# Sensor_Probe_Panel.net
KiCad netlist of a schematic drawn in Altium Designer
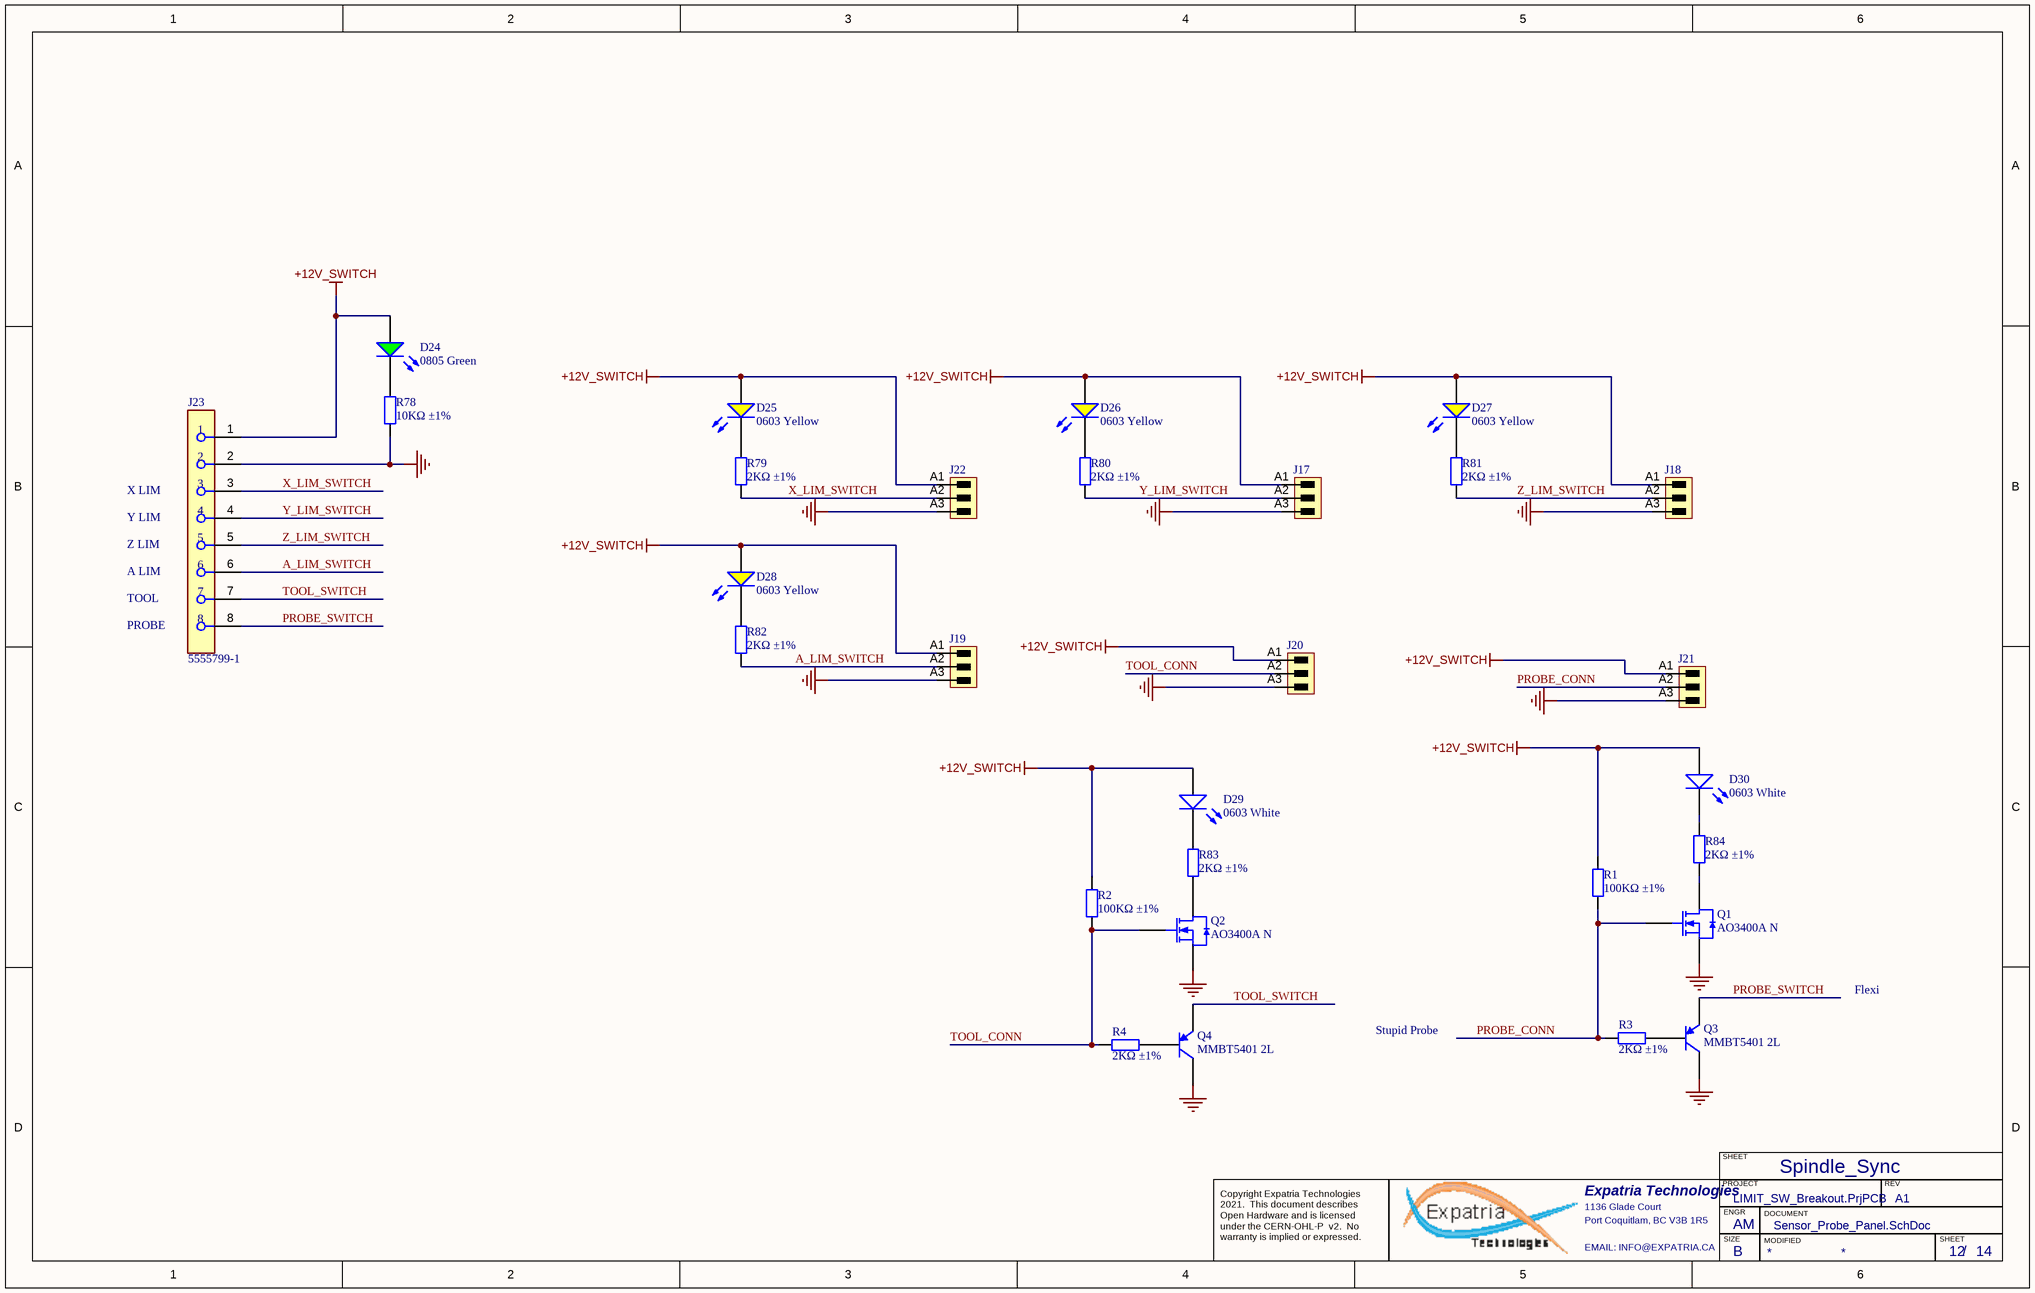
[diagram p0: Sensor_Probe_Panel.SchDoc]

(export (version "E")
  (design (tool "Eeschema 10.0.6"))
  (components
    (comp (ref "D24")
      (value "0805 Green")
      (footprint "0805_LED_S1")
      (description "LED")
      (libsource (lib "LED") (part "0805 LED Green"))
    )
    (comp (ref "D25")
      (value "0603 Yellow")
      (footprint "0603_LED_S1")
      (description "LED")
      (libsource (lib "LED") (part "0603 LED Yellow"))
    )
    (comp (ref "D26")
      (value "0603 Yellow")
      (footprint "0603_LED_S1")
      (description "LED")
      (libsource (lib "LED") (part "0603 LED Yellow"))
    )
    (comp (ref "D27")
      (value "0603 Yellow")
      (footprint "0603_LED_S1")
      (description "LED")
      (libsource (lib "LED") (part "0603 LED Yellow"))
    )
    (comp (ref "D28")
      (value "0603 Yellow")
      (footprint "0603_LED_S1")
      (description "LED")
      (libsource (lib "LED") (part "0603 LED Yellow"))
    )
    (comp (ref "D29")
      (value "0603 White")
      (footprint "0603_LED_S1")
      (description "LED")
      (libsource (lib "LED") (part "0603 LED White"))
    )
    (comp (ref "D30")
      (value "0603 White")
      (footprint "0603_LED_S1")
      (description "LED")
      (libsource (lib "LED") (part "0603 LED White"))
    )
    (comp (ref "J17")
      (value "~")
      (footprint "SL_3_50_180G_03")
      (fields
        (field (name "PARTNUMBER") "WJ15EDGVC-3.5-3P")
        (field (name "MANUFACTURER") "Ningbo Kangnex Elec")
      )
      (libsource (lib "PrintNC_GRBLHAL_Breakout") (part "Header_Male_03_1x03"))
    )
    (comp (ref "J18")
      (value "~")
      (footprint "SL_3_50_180G_03")
      (fields
        (field (name "PARTNUMBER") "WJ15EDGVC-3.5-3P")
        (field (name "MANUFACTURER") "Ningbo Kangnex Elec")
      )
      (libsource (lib "PrintNC_GRBLHAL_Breakout") (part "Header_Male_03_1x03"))
    )
    (comp (ref "J19")
      (value "~")
      (footprint "SL_3_50_180G_03")
      (fields
        (field (name "PARTNUMBER") "WJ15EDGVC-3.5-3P")
        (field (name "MANUFACTURER") "Ningbo Kangnex Elec")
      )
      (libsource (lib "PrintNC_GRBLHAL_Breakout") (part "Header_Male_03_1x03"))
    )
    (comp (ref "J20")
      (value "~")
      (footprint "SL_3_50_180G_03")
      (fields
        (field (name "PARTNUMBER") "WJ15EDGVC-3.5-3P")
        (field (name "MANUFACTURER") "Ningbo Kangnex Elec")
      )
      (libsource (lib "PrintNC_GRBLHAL_Breakout") (part "Header_Male_03_1x03"))
    )
    (comp (ref "J21")
      (value "~")
      (footprint "SL_3_50_180G_03")
      (fields
        (field (name "PARTNUMBER") "WJ15EDGVC-3.5-3P")
        (field (name "MANUFACTURER") "Ningbo Kangnex Elec")
      )
      (libsource (lib "PrintNC_GRBLHAL_Breakout") (part "Header_Male_03_1x03"))
    )
    (comp (ref "J22")
      (value "~")
      (footprint "SL_3_50_180G_03")
      (fields
        (field (name "PARTNUMBER") "WJ15EDGVC-3.5-3P")
        (field (name "MANUFACTURER") "Ningbo Kangnex Elec")
      )
      (libsource (lib "PrintNC_GRBLHAL_Breakout") (part "Header_Male_03_1x03"))
    )
    (comp (ref "J23")
      (value "5555799-1")
      (footprint "FP-5555799-1-MFG")
      (description "CONN MOD JACK 8P8C VERT UNSHLD")
      (fields
        (field (name "MANUFACTURER") "TE Connectivity")
        (field (name "OCTOPART") "https://octopart.com/5555799-1-te+connectivity-39526335")
      )
      (libsource (lib "PrintNC_GRBLHAL_Breakout") (part "a32a9c29f5c2290c50060dfb8ad7212"))
    )
    (comp (ref "Q1")
      (value "AO3400A N")
      (footprint "SOT-23-3L")
      (description "MOS(场效应管)")
      (libsource (lib "MOS") (part "AO3400A N道沟 X0YV1T SOT-23"))
    )
    (comp (ref "Q2")
      (value "AO3400A N")
      (footprint "SOT-23-3L")
      (description "MOS(场效应管)")
      (libsource (lib "MOS") (part "AO3400A N道沟 X0YV1T SOT-23"))
    )
    (comp (ref "Q3")
      (value "MMBT5401 2L")
      (footprint "SOT-23(SOT-23-3)")
      (description "三极管")
      (libsource (lib "Transistor_PNP") (part "SOT-23 MMBT5401 2L"))
    )
    (comp (ref "Q4")
      (value "MMBT5401 2L")
      (footprint "SOT-23(SOT-23-3)")
      (description "三极管")
      (libsource (lib "Transistor_PNP") (part "SOT-23 MMBT5401 2L"))
    )
    (comp (ref "R1")
      (value "100KΩ ±1%")
      (footprint "0603_R")
      (description "Chip resistor")
      (fields (field (name "MANUFACTURER") "Uniroyal Elec") (field (name "PARTNUMBER") "0603WAF1003T5E"))
      (libsource (lib "RES") (part "0603 100K (1003) 1%"))
    )
    (comp (ref "R2")
      (value "100KΩ ±1%")
      (footprint "0603_R")
      (description "Chip resistor")
      (fields (field (name "MANUFACTURER") "Uniroyal Elec") (field (name "PARTNUMBER") "0603WAF1003T5E"))
      (libsource (lib "RES") (part "0603 100K (1003) 1%"))
    )
    (comp (ref "R3")
      (value "2KΩ ±1%")
      (footprint "0603_R")
      (description "Chip resistor")
      (fields (field (name "MANUFACTURER") "Uniroyal Elec") (field (name "PARTNUMBER") "0603WAF2001T5E"))
      (libsource (lib "") (part "0603 2K (2001) 1%_1"))
    )
    (comp (ref "R4")
      (value "2KΩ ±1%")
      (footprint "0603_R")
      (description "Chip resistor")
      (fields (field (name "MANUFACTURER") "Uniroyal Elec") (field (name "PARTNUMBER") "0603WAF2001T5E"))
      (libsource (lib "") (part "0603 2K (2001) 1%_1"))
    )
    (comp (ref "R78")
      (value "10KΩ ±1%")
      (footprint "0603_R")
      (description "Chip resistor")
      (fields (field (name "MANUFACTURER") "Uniroyal Elec") (field (name "PARTNUMBER") "0603WAF1002T5E"))
      (libsource (lib "PrintNC_GRBLHAL_Breakout") (part "0603 10K (1002) 1%"))
    )
    (comp (ref "R79")
      (value "2KΩ ±1%")
      (footprint "0603_R")
      (description "Chip resistor")
      (fields (field (name "MANUFACTURER") "Uniroyal Elec") (field (name "PARTNUMBER") "0603WAF2001T5E"))
      (libsource (lib "PrintNC_GRBLHAL_Breakout") (part "0603 2K (2001) 1%"))
    )
    (comp (ref "R80")
      (value "2KΩ ±1%")
      (footprint "0603_R")
      (description "Chip resistor")
      (fields (field (name "MANUFACTURER") "Uniroyal Elec") (field (name "PARTNUMBER") "0603WAF2001T5E"))
      (libsource (lib "PrintNC_GRBLHAL_Breakout") (part "0603 2K (2001) 1%"))
    )
    (comp (ref "R81")
      (value "2KΩ ±1%")
      (footprint "0603_R")
      (description "Chip resistor")
      (fields (field (name "MANUFACTURER") "Uniroyal Elec") (field (name "PARTNUMBER") "0603WAF2001T5E"))
      (libsource (lib "PrintNC_GRBLHAL_Breakout") (part "0603 2K (2001) 1%"))
    )
    (comp (ref "R82")
      (value "2KΩ ±1%")
      (footprint "0603_R")
      (description "Chip resistor")
      (fields (field (name "MANUFACTURER") "Uniroyal Elec") (field (name "PARTNUMBER") "0603WAF2001T5E"))
      (libsource (lib "PrintNC_GRBLHAL_Breakout") (part "0603 2K (2001) 1%"))
    )
    (comp (ref "R83")
      (value "2KΩ ±1%")
      (footprint "0603_R")
      (description "Chip resistor")
      (fields (field (name "MANUFACTURER") "Uniroyal Elec") (field (name "PARTNUMBER") "0603WAF2001T5E"))
      (libsource (lib "PrintNC_GRBLHAL_Breakout") (part "0603 2K (2001) 1%"))
    )
    (comp (ref "R84")
      (value "2KΩ ±1%")
      (footprint "0603_R")
      (description "Chip resistor")
      (fields (field (name "MANUFACTURER") "Uniroyal Elec") (field (name "PARTNUMBER") "0603WAF2001T5E"))
      (libsource (lib "PrintNC_GRBLHAL_Breakout") (part "0603 2K (2001) 1%"))
    )
  )
  (nets
    (net (code "1") (name "+12V_SWITCH") (class "Default")
      (node (ref "D24") (pin "A") (pinfunction "A_A") (pintype "passive"))
      (node (ref "D25") (pin "A") (pinfunction "A_A") (pintype "passive"))
      (node (ref "D26") (pin "A") (pinfunction "A_A") (pintype "passive"))
      (node (ref "D27") (pin "A") (pinfunction "A_A") (pintype "passive"))
      (node (ref "D28") (pin "A") (pinfunction "A_A") (pintype "passive"))
      (node (ref "D29") (pin "A") (pinfunction "A_A") (pintype "passive"))
      (node (ref "D30") (pin "A") (pinfunction "A_A") (pintype "passive"))
      (node (ref "J17") (pin "A1") (pinfunction "A1_A1") (pintype "passive"))
      (node (ref "J18") (pin "A1") (pinfunction "A1_A1") (pintype "passive"))
      (node (ref "J19") (pin "A1") (pinfunction "A1_A1") (pintype "passive"))
      (node (ref "J20") (pin "A1") (pinfunction "A1_A1") (pintype "passive"))
      (node (ref "J21") (pin "A1") (pinfunction "A1_A1") (pintype "passive"))
      (node (ref "J22") (pin "A1") (pinfunction "A1_A1") (pintype "passive"))
      (node (ref "J23") (pin "1") (pinfunction "1_1") (pintype "passive"))
      (node (ref "R1") (pin "2") (pinfunction "2_2") (pintype "passive"))
      (node (ref "R2") (pin "2") (pinfunction "2_2") (pintype "passive"))
    )
    (net (code "2") (name "/A_LIM_SWITCH") (class "Default")
      (node (ref "J19") (pin "A2") (pinfunction "A2_A2") (pintype "passive"))
      (node (ref "J23") (pin "6") (pinfunction "6_6") (pintype "passive"))
      (node (ref "R82") (pin "2") (pinfunction "2_2") (pintype "passive"))
    )
    (net (code "3") (name "/PROBE_CONN") (class "Default")
      (node (ref "J21") (pin "A2") (pinfunction "A2_A2") (pintype "passive"))
      (node (ref "Q1") (pin "1") (pinfunction "G_1") (pintype "passive"))
      (node (ref "R1") (pin "1") (pinfunction "1_1") (pintype "passive"))
      (node (ref "R3") (pin "1") (pinfunction "1_1") (pintype "passive"))
    )
    (net (code "4") (name "/PROBE_SWITCH") (class "Default")
      (node (ref "J23") (pin "8") (pinfunction "8_8") (pintype "passive"))
      (node (ref "Q3") (pin "2") (pinfunction "E_2") (pintype "passive"))
    )
    (net (code "5") (name "/TOOL_CONN") (class "Default")
      (node (ref "J20") (pin "A2") (pinfunction "A2_A2") (pintype "passive"))
      (node (ref "Q2") (pin "1") (pinfunction "G_1") (pintype "passive"))
      (node (ref "R2") (pin "1") (pinfunction "1_1") (pintype "passive"))
      (node (ref "R4") (pin "1") (pinfunction "1_1") (pintype "passive"))
    )
    (net (code "6") (name "/TOOL_SWITCH") (class "Default")
      (node (ref "J23") (pin "7") (pinfunction "7_7") (pintype "passive"))
      (node (ref "Q4") (pin "2") (pinfunction "E_2") (pintype "passive"))
    )
    (net (code "7") (name "/X_LIM_SWITCH") (class "Default")
      (node (ref "J22") (pin "A2") (pinfunction "A2_A2") (pintype "passive"))
      (node (ref "J23") (pin "3") (pinfunction "3_3") (pintype "passive"))
      (node (ref "R79") (pin "2") (pinfunction "2_2") (pintype "passive"))
    )
    (net (code "8") (name "/Y_LIM_SWITCH") (class "Default")
      (node (ref "J17") (pin "A2") (pinfunction "A2_A2") (pintype "passive"))
      (node (ref "J23") (pin "4") (pinfunction "4_4") (pintype "passive"))
      (node (ref "R80") (pin "2") (pinfunction "2_2") (pintype "passive"))
    )
    (net (code "9") (name "/Z_LIM_SWITCH") (class "Default")
      (node (ref "J18") (pin "A2") (pinfunction "A2_A2") (pintype "passive"))
      (node (ref "J23") (pin "5") (pinfunction "5_5") (pintype "passive"))
      (node (ref "R81") (pin "2") (pinfunction "2_2") (pintype "passive"))
    )
    (net (code "10") (name "GND_SWITCH") (class "Default")
      (node (ref "J17") (pin "A3") (pinfunction "A3_A3") (pintype "passive"))
      (node (ref "J18") (pin "A3") (pinfunction "A3_A3") (pintype "passive"))
      (node (ref "J19") (pin "A3") (pinfunction "A3_A3") (pintype "passive"))
      (node (ref "J20") (pin "A3") (pinfunction "A3_A3") (pintype "passive"))
      (node (ref "J21") (pin "A3") (pinfunction "A3_A3") (pintype "passive"))
      (node (ref "J22") (pin "A3") (pinfunction "A3_A3") (pintype "passive"))
      (node (ref "J23") (pin "2") (pinfunction "2_2") (pintype "passive"))
      (node (ref "Q1") (pin "2") (pinfunction "S_2") (pintype "passive"))
      (node (ref "Q2") (pin "2") (pinfunction "S_2") (pintype "passive"))
      (node (ref "Q3") (pin "3") (pinfunction "C_3") (pintype "passive"))
      (node (ref "Q4") (pin "3") (pinfunction "C_3") (pintype "passive"))
      (node (ref "R78") (pin "1") (pinfunction "1_1") (pintype "passive"))
    )
    (net (code "11") (name "Net-(D24-PadK)") (class "Default")
      (node (ref "D24") (pin "K") (pinfunction "K_K") (pintype "passive"))
      (node (ref "R78") (pin "2") (pinfunction "2_2") (pintype "passive"))
    )
    (net (code "12") (name "Net-(D25-PadK)") (class "Default")
      (node (ref "D25") (pin "K") (pinfunction "K_K") (pintype "passive"))
      (node (ref "R79") (pin "1") (pinfunction "1_1") (pintype "passive"))
    )
    (net (code "13") (name "Net-(D26-PadK)") (class "Default")
      (node (ref "D26") (pin "K") (pinfunction "K_K") (pintype "passive"))
      (node (ref "R80") (pin "1") (pinfunction "1_1") (pintype "passive"))
    )
    (net (code "14") (name "Net-(D27-PadK)") (class "Default")
      (node (ref "D27") (pin "K") (pinfunction "K_K") (pintype "passive"))
      (node (ref "R81") (pin "1") (pinfunction "1_1") (pintype "passive"))
    )
    (net (code "15") (name "Net-(D28-PadK)") (class "Default")
      (node (ref "D28") (pin "K") (pinfunction "K_K") (pintype "passive"))
      (node (ref "R82") (pin "1") (pinfunction "1_1") (pintype "passive"))
    )
    (net (code "16") (name "Net-(D29-PadK)") (class "Default")
      (node (ref "D29") (pin "K") (pinfunction "K_K") (pintype "passive"))
      (node (ref "R83") (pin "1") (pinfunction "1_1") (pintype "passive"))
    )
    (net (code "17") (name "Net-(D30-PadK)") (class "Default")
      (node (ref "D30") (pin "K") (pinfunction "K_K") (pintype "passive"))
      (node (ref "R84") (pin "1") (pinfunction "1_1") (pintype "passive"))
    )
    (net (code "18") (name "Net-(Q1-D)") (class "Default")
      (node (ref "Q1") (pin "3") (pinfunction "D_3") (pintype "passive"))
      (node (ref "R84") (pin "2") (pinfunction "2_2") (pintype "passive"))
    )
    (net (code "19") (name "Net-(Q2-D)") (class "Default")
      (node (ref "Q2") (pin "3") (pinfunction "D_3") (pintype "passive"))
      (node (ref "R83") (pin "2") (pinfunction "2_2") (pintype "passive"))
    )
    (net (code "20") (name "Net-(Q3-B)") (class "Default")
      (node (ref "Q3") (pin "1") (pinfunction "B_1") (pintype "passive"))
      (node (ref "R3") (pin "2") (pinfunction "2_2") (pintype "passive"))
    )
    (net (code "21") (name "Net-(Q4-B)") (class "Default")
      (node (ref "Q4") (pin "1") (pinfunction "B_1") (pintype "passive"))
      (node (ref "R4") (pin "2") (pinfunction "2_2") (pintype "passive"))
    )
  )
)
